# HVDCS_S3A6_48_TQFP_v1p01.net
KiCad netlist of a schematic drawn in EAGLE
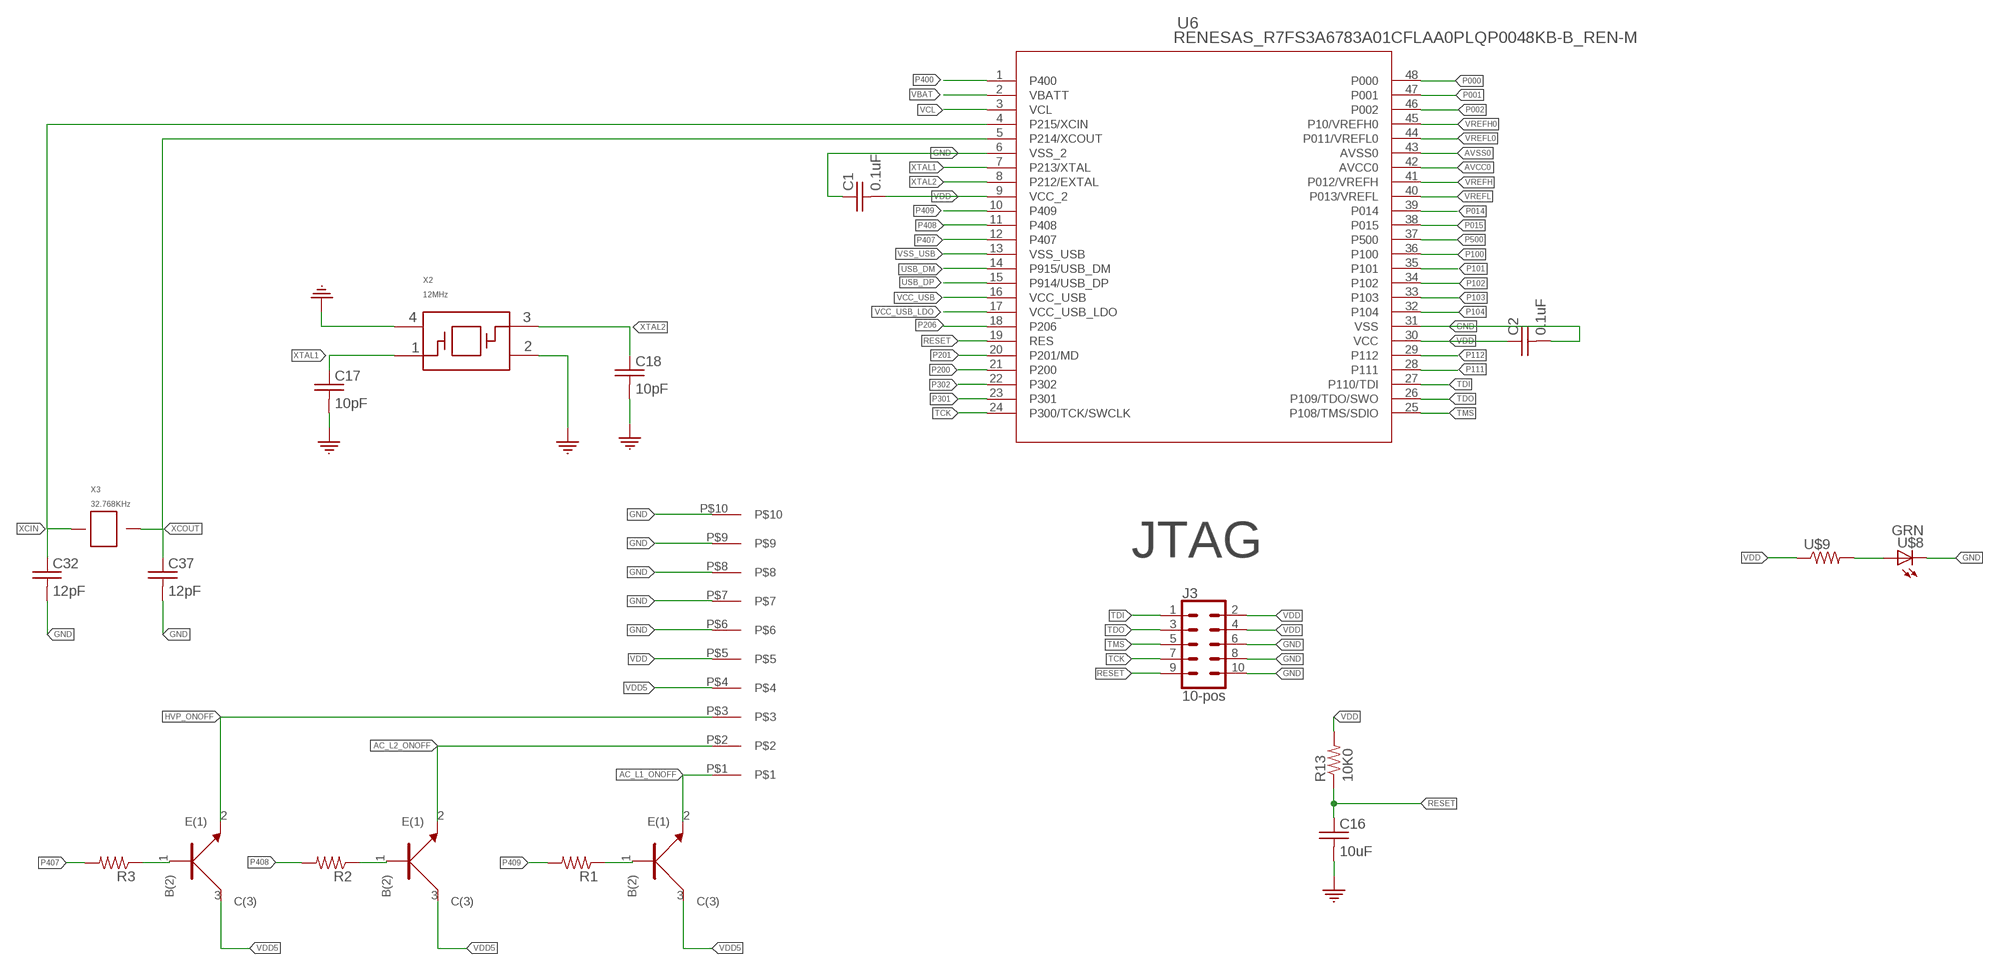
[diagram p0: schematic, sheet 1]

(export (version "E")
  (design (tool "Eeschema 10.0.6"))
  (components
    (comp (ref "C1")
      (value "0.1uF")
      (footprint "eagle-import:0402")
      (fields (field (name "PARTNO") "CL05F104ZO5NNNC"))
      (libsource (lib "eagle-import") (part "C_0402_0.1UF"))
    )
    (comp (ref "C2")
      (value "0.1uF")
      (footprint "eagle-import:0402")
      (fields (field (name "PARTNO") "CL05F104ZO5NNNC"))
      (libsource (lib "eagle-import") (part "C_0402_0.1UF"))
    )
    (comp (ref "C16")
      (value "10uF")
      (footprint "eagle-import:0402")
      (fields (field (name "PARTNO") "CL05A106MP8NUB8"))
      (libsource (lib "eagle-import") (part "C_0402_10UF"))
    )
    (comp (ref "C17")
      (value "10pF")
      (footprint "eagle-import:0402")
      (fields (field (name "PARTNO") "UMK105CG180JV-F"))
      (libsource (lib "eagle-import") (part "C_0402_18PF"))
    )
    (comp (ref "C18")
      (value "10pF")
      (footprint "eagle-import:0402")
      (fields (field (name "PARTNO") "UMK105CG180JV-F"))
      (libsource (lib "eagle-import") (part "C_0402_18PF"))
    )
    (comp (ref "C32")
      (value "12pF")
      (footprint "eagle-import:0402")
      (fields (field (name "PARTNO") "CL05C120JB5NNNC"))
      (libsource (lib "eagle-import") (part "C_0402_12PF"))
    )
    (comp (ref "C37")
      (value "12pF")
      (footprint "eagle-import:0402")
      (fields (field (name "PARTNO") "CL05C120JB5NNNC"))
      (libsource (lib "eagle-import") (part "C_0402_12PF"))
    )
    (comp (ref "J3")
      (value "10-pos")
      (footprint "eagle-import:2X5")
      (fields (field (name "PARTNO") "PH2RA-10-UA"))
      (libsource (lib "eagle-import") (part "CONN_05X2_RAPTH"))
    )
    (comp (ref "R1")
      (value "R_0402")
      (footprint "eagle-import:0402")
      (libsource (lib "eagle-import") (part "R_0402"))
    )
    (comp (ref "R2")
      (value "R_0402")
      (footprint "eagle-import:0402")
      (libsource (lib "eagle-import") (part "R_0402"))
    )
    (comp (ref "R3")
      (value "R_0402")
      (footprint "eagle-import:0402")
      (libsource (lib "eagle-import") (part "R_0402"))
    )
    (comp (ref "R13")
      (value "10K0")
      (footprint "eagle-import:0402")
      (fields (field (name "PARTNO") "RMCF0402JT10K0"))
      (libsource (lib "eagle-import") (part "R_0402_10K0"))
    )
    (comp (ref "U$5")
      (value "1_X_10_HEADER_GENERIC_.1INCH")
      (footprint "eagle-import:HEADER_1_X_10_.1_INCH")
      (libsource (lib "eagle-import") (part "1_X_10_HEADER_GENERIC_.1INCH"))
    )
    (comp (ref "U$8")
      (value "LED_0805_GREEN")
      (footprint "eagle-import:LED_0805_GREEN")
      (libsource (lib "eagle-import") (part "LED_0805_GREEN"))
    )
    (comp (ref "U$9")
      (value "470R0")
      (footprint "eagle-import:0402")
      (fields (field (name "PARTNO") "RMCF0402JT470R"))
      (libsource (lib "eagle-import") (part "R_0402_470R0"))
    )
    (comp (ref "U1")
      (value "NPN")
      (footprint "eagle-import:SOT323")
      (fields (field (name "PARTNO") "BC846BW_NPN"))
      (libsource (lib "eagle-import") (part "BC846BW"))
    )
    (comp (ref "U2")
      (value "NPN")
      (footprint "eagle-import:SOT323")
      (fields (field (name "PARTNO") "BC846BW_NPN"))
      (libsource (lib "eagle-import") (part "BC846BW"))
    )
    (comp (ref "U3")
      (value "NPN")
      (footprint "eagle-import:SOT323")
      (fields (field (name "PARTNO") "BC846BW_NPN"))
      (libsource (lib "eagle-import") (part "BC846BW"))
    )
    (comp (ref "U6")
      (value "RENESAS_R7FS3A6783A01CFLAA0PLQP0048KB-B_REN-M")
      (footprint "eagle-import:PLQP0048KB-B_REN-M")
      (fields
        (field (name "MANUFACTURER_PART_NUMBER") "R7FS3A6783A01CFL#AA0")
        (field (name "COPYRIGHT") "Copyright (C) 2021 Accelerated Designs. All rights reserved")
      )
      (libsource (lib "eagle-import") (part "RENESAS_R7FS3A6783A01CFLAA0PLQP0048KB-B_REN-M"))
    )
    (comp (ref "X2")
      (value "12MHz")
      (footprint "eagle-import:SMD_3225")
      (fields (field (name "PARTNO") "FA-238 24.0000MB-C3 "))
      (libsource (lib "eagle-import") (part "XTAL_24_MHZ"))
    )
    (comp (ref "X3")
      (value "32.768KHz")
      (footprint "eagle-import:SMD_X_2_PADS")
      (fields (field (name "PARTNO") "ABS07-32.768KHZ-T"))
      (libsource (lib "eagle-import") (part "XTAL_32.768KHZ"))
    )
  )
  (nets
    (net (code "1") (name "AC_L1_ONOFF") (class "Default")
      (node (ref "U$5") (pin "P$1") (pinfunction "P$1_P$1") (pintype "bidirectional"))
      (node (ref "U1") (pin "2") (pinfunction "E(1)_2") (pintype "output"))
    )
    (net (code "2") (name "AC_L2_ONOFF") (class "Default")
      (node (ref "U$5") (pin "P$2") (pinfunction "P$2_P$2") (pintype "bidirectional"))
      (node (ref "U2") (pin "2") (pinfunction "E(1)_2") (pintype "output"))
    )
    (net (code "3") (name "AVCC0") (class "Default")
      (node (ref "U6") (pin "42") (pinfunction "AVCC0_42") (pintype "power_in"))
    )
    (net (code "4") (name "AVSS0") (class "Default")
      (node (ref "U6") (pin "43") (pinfunction "AVSS0_43") (pintype "passive"))
    )
    (net (code "5") (name "GND") (class "Default")
      (node (ref "C1") (pin "P$1") (pinfunction "1_P$1") (pintype "passive"))
      (node (ref "C16") (pin "P$2") (pinfunction "2_P$2") (pintype "passive"))
      (node (ref "C17") (pin "P$2") (pinfunction "2_P$2") (pintype "passive"))
      (node (ref "C18") (pin "P$2") (pinfunction "2_P$2") (pintype "passive"))
      (node (ref "C2") (pin "P$2") (pinfunction "2_P$2") (pintype "passive"))
      (node (ref "C32") (pin "P$2") (pinfunction "2_P$2") (pintype "passive"))
      (node (ref "C37") (pin "P$2") (pinfunction "2_P$2") (pintype "passive"))
      (node (ref "J3") (pin "10") (pinfunction "10_10") (pintype "passive"))
      (node (ref "J3") (pin "6") (pinfunction "6_6") (pintype "passive"))
      (node (ref "J3") (pin "8") (pinfunction "8_8") (pintype "passive"))
      (node (ref "U$5") (pin "P$10") (pinfunction "P$10_P$10") (pintype "bidirectional"))
      (node (ref "U$5") (pin "P$6") (pinfunction "P$6_P$6") (pintype "bidirectional"))
      (node (ref "U$5") (pin "P$7") (pinfunction "P$7_P$7") (pintype "bidirectional"))
      (node (ref "U$5") (pin "P$8") (pinfunction "P$8_P$8") (pintype "bidirectional"))
      (node (ref "U$5") (pin "P$9") (pinfunction "P$9_P$9") (pintype "bidirectional"))
      (node (ref "U$8") (pin "C") (pinfunction "C_C") (pintype "passive"))
      (node (ref "U6") (pin "31") (pinfunction "VSS_31") (pintype "passive"))
      (node (ref "U6") (pin "6") (pinfunction "VSS_2_6") (pintype "passive"))
      (node (ref "X2") (pin "2") (pinfunction "2_2") (pintype "bidirectional"))
      (node (ref "X2") (pin "4") (pinfunction "4_4") (pintype "bidirectional"))
    )
    (net (code "6") (name "HVP_ONOFF") (class "Default")
      (node (ref "U$5") (pin "P$3") (pinfunction "P$3_P$3") (pintype "bidirectional"))
      (node (ref "U3") (pin "2") (pinfunction "E(1)_2") (pintype "output"))
    )
    (net (code "7") (name "Net-(R1-1)") (class "Default")
      (node (ref "R1") (pin "P$1") (pinfunction "1_P$1") (pintype "passive"))
      (node (ref "U1") (pin "1") (pinfunction "B(2)_1") (pintype "input"))
    )
    (net (code "8") (name "Net-(R2-1)") (class "Default")
      (node (ref "R2") (pin "P$1") (pinfunction "1_P$1") (pintype "passive"))
      (node (ref "U2") (pin "1") (pinfunction "B(2)_1") (pintype "input"))
    )
    (net (code "9") (name "Net-(R3-1)") (class "Default")
      (node (ref "R3") (pin "P$1") (pinfunction "1_P$1") (pintype "passive"))
      (node (ref "U3") (pin "1") (pinfunction "B(2)_1") (pintype "input"))
    )
    (net (code "10") (name "Net-(U$9-2)") (class "Default")
      (node (ref "U$8") (pin "A") (pinfunction "A_A") (pintype "passive"))
      (node (ref "U$9") (pin "P$2") (pinfunction "2_P$2") (pintype "passive"))
    )
    (net (code "11") (name "P000") (class "Default")
      (node (ref "U6") (pin "48") (pinfunction "P000_48") (pintype "bidirectional"))
    )
    (net (code "12") (name "P001") (class "Default")
      (node (ref "U6") (pin "47") (pinfunction "P001_47") (pintype "bidirectional"))
    )
    (net (code "13") (name "P002") (class "Default")
      (node (ref "U6") (pin "46") (pinfunction "P002_46") (pintype "bidirectional"))
    )
    (net (code "14") (name "P014") (class "Default")
      (node (ref "U6") (pin "39") (pinfunction "P014_39") (pintype "bidirectional"))
    )
    (net (code "15") (name "P015") (class "Default")
      (node (ref "U6") (pin "38") (pinfunction "P015_38") (pintype "bidirectional"))
    )
    (net (code "16") (name "P100") (class "Default")
      (node (ref "U6") (pin "36") (pinfunction "P100_36") (pintype "bidirectional"))
    )
    (net (code "17") (name "P101") (class "Default")
      (node (ref "U6") (pin "35") (pinfunction "P101_35") (pintype "bidirectional"))
    )
    (net (code "18") (name "P102") (class "Default")
      (node (ref "U6") (pin "34") (pinfunction "P102_34") (pintype "bidirectional"))
    )
    (net (code "19") (name "P103") (class "Default")
      (node (ref "U6") (pin "33") (pinfunction "P103_33") (pintype "bidirectional"))
    )
    (net (code "20") (name "P104") (class "Default")
      (node (ref "U6") (pin "32") (pinfunction "P104_32") (pintype "bidirectional"))
    )
    (net (code "21") (name "P111") (class "Default")
      (node (ref "U6") (pin "28") (pinfunction "P111_28") (pintype "bidirectional"))
    )
    (net (code "22") (name "P112") (class "Default")
      (node (ref "U6") (pin "29") (pinfunction "P112_29") (pintype "bidirectional"))
    )
    (net (code "23") (name "P200") (class "Default")
      (node (ref "U6") (pin "21") (pinfunction "P200_21") (pintype "bidirectional"))
    )
    (net (code "24") (name "P201") (class "Default")
      (node (ref "U6") (pin "20") (pinfunction "P201/MD_20") (pintype "bidirectional"))
    )
    (net (code "25") (name "P206") (class "Default")
      (node (ref "U6") (pin "18") (pinfunction "P206_18") (pintype "bidirectional"))
    )
    (net (code "26") (name "P301") (class "Default")
      (node (ref "U6") (pin "23") (pinfunction "P301_23") (pintype "bidirectional"))
    )
    (net (code "27") (name "P302") (class "Default")
      (node (ref "U6") (pin "22") (pinfunction "P302_22") (pintype "bidirectional"))
    )
    (net (code "28") (name "P400") (class "Default")
      (node (ref "U6") (pin "1") (pinfunction "P400_1") (pintype "bidirectional"))
    )
    (net (code "29") (name "P407") (class "Default")
      (node (ref "R3") (pin "P$2") (pinfunction "2_P$2") (pintype "passive"))
      (node (ref "U6") (pin "12") (pinfunction "P407_12") (pintype "bidirectional"))
    )
    (net (code "30") (name "P408") (class "Default")
      (node (ref "R2") (pin "P$2") (pinfunction "2_P$2") (pintype "passive"))
      (node (ref "U6") (pin "11") (pinfunction "P408_11") (pintype "bidirectional"))
    )
    (net (code "31") (name "P409") (class "Default")
      (node (ref "R1") (pin "P$2") (pinfunction "2_P$2") (pintype "passive"))
      (node (ref "U6") (pin "10") (pinfunction "P409_10") (pintype "bidirectional"))
    )
    (net (code "32") (name "P500") (class "Default")
      (node (ref "U6") (pin "37") (pinfunction "P500_37") (pintype "bidirectional"))
    )
    (net (code "33") (name "RESET") (class "Default")
      (node (ref "C16") (pin "P$1") (pinfunction "1_P$1") (pintype "passive"))
      (node (ref "J3") (pin "9") (pinfunction "9_9") (pintype "passive"))
      (node (ref "R13") (pin "P$1") (pinfunction "1_P$1") (pintype "passive"))
      (node (ref "U6") (pin "19") (pinfunction "RES_19") (pintype "passive"))
    )
    (net (code "34") (name "TCK") (class "Default")
      (node (ref "J3") (pin "7") (pinfunction "7_7") (pintype "passive"))
      (node (ref "U6") (pin "24") (pinfunction "P300/TCK/SWCLK_24") (pintype "bidirectional"))
    )
    (net (code "35") (name "TDI") (class "Default")
      (node (ref "J3") (pin "1") (pinfunction "1_1") (pintype "passive"))
      (node (ref "U6") (pin "27") (pinfunction "P110/TDI_27") (pintype "bidirectional"))
    )
    (net (code "36") (name "TDO") (class "Default")
      (node (ref "J3") (pin "3") (pinfunction "3_3") (pintype "passive"))
      (node (ref "U6") (pin "26") (pinfunction "P109/TDO/SWO_26") (pintype "bidirectional"))
    )
    (net (code "37") (name "TMS") (class "Default")
      (node (ref "J3") (pin "5") (pinfunction "5_5") (pintype "passive"))
      (node (ref "U6") (pin "25") (pinfunction "P108/TMS/SDIO_25") (pintype "bidirectional"))
    )
    (net (code "38") (name "USB_DM") (class "Default")
      (node (ref "U6") (pin "14") (pinfunction "P915/USB_DM_14") (pintype "bidirectional"))
    )
    (net (code "39") (name "USB_DP") (class "Default")
      (node (ref "U6") (pin "15") (pinfunction "P914/USB_DP_15") (pintype "bidirectional"))
    )
    (net (code "40") (name "VBAT") (class "Default")
      (node (ref "U6") (pin "2") (pinfunction "VBATT_2") (pintype "passive"))
    )
    (net (code "41") (name "VCC_USB") (class "Default")
      (node (ref "U6") (pin "16") (pinfunction "VCC_USB_16") (pintype "power_in"))
    )
    (net (code "42") (name "VCC_USB_LDO") (class "Default")
      (node (ref "U6") (pin "17") (pinfunction "VCC_USB_LDO_17") (pintype "power_in"))
    )
    (net (code "43") (name "VCL") (class "Default")
      (node (ref "U6") (pin "3") (pinfunction "VCL_3") (pintype "passive"))
    )
    (net (code "44") (name "VDD") (class "Default")
      (node (ref "C1") (pin "P$2") (pinfunction "2_P$2") (pintype "passive"))
      (node (ref "C2") (pin "P$1") (pinfunction "1_P$1") (pintype "passive"))
      (node (ref "J3") (pin "2") (pinfunction "2_2") (pintype "passive"))
      (node (ref "J3") (pin "4") (pinfunction "4_4") (pintype "passive"))
      (node (ref "R13") (pin "P$2") (pinfunction "2_P$2") (pintype "passive"))
      (node (ref "U$5") (pin "P$5") (pinfunction "P$5_P$5") (pintype "bidirectional"))
      (node (ref "U$9") (pin "P$1") (pinfunction "1_P$1") (pintype "passive"))
      (node (ref "U6") (pin "30") (pinfunction "VCC_30") (pintype "power_in"))
      (node (ref "U6") (pin "9") (pinfunction "VCC_2_9") (pintype "power_in"))
    )
    (net (code "45") (name "VDD5") (class "Default")
      (node (ref "U$5") (pin "P$4") (pinfunction "P$4_P$4") (pintype "bidirectional"))
      (node (ref "U1") (pin "3") (pinfunction "C(3)_3") (pintype "input"))
      (node (ref "U2") (pin "3") (pinfunction "C(3)_3") (pintype "input"))
      (node (ref "U3") (pin "3") (pinfunction "C(3)_3") (pintype "input"))
    )
    (net (code "46") (name "VREFH") (class "Default")
      (node (ref "U6") (pin "41") (pinfunction "P012/VREFH_41") (pintype "power_in"))
    )
    (net (code "47") (name "VREFH0") (class "Default")
      (node (ref "U6") (pin "45") (pinfunction "P10/VREFH0_45") (pintype "power_in"))
    )
    (net (code "48") (name "VREFL") (class "Default")
      (node (ref "U6") (pin "40") (pinfunction "P013/VREFL_40") (pintype "power_in"))
    )
    (net (code "49") (name "VREFL0") (class "Default")
      (node (ref "U6") (pin "44") (pinfunction "P011/VREFL0_44") (pintype "power_in"))
    )
    (net (code "50") (name "VSS_USB") (class "Default")
      (node (ref "U6") (pin "13") (pinfunction "VSS_USB_13") (pintype "passive"))
    )
    (net (code "51") (name "XCIN") (class "Default")
      (node (ref "C32") (pin "P$1") (pinfunction "1_P$1") (pintype "passive"))
      (node (ref "U6") (pin "4") (pinfunction "P215/XCIN_4") (pintype "bidirectional"))
      (node (ref "X3") (pin "P$1") (pinfunction "P$1_P$1") (pintype "bidirectional"))
    )
    (net (code "52") (name "XCOUT") (class "Default")
      (node (ref "C37") (pin "P$1") (pinfunction "1_P$1") (pintype "passive"))
      (node (ref "U6") (pin "5") (pinfunction "P214/XCOUT_5") (pintype "output"))
      (node (ref "X3") (pin "P$2") (pinfunction "P$2_P$2") (pintype "bidirectional"))
    )
    (net (code "53") (name "XTAL1") (class "Default")
      (node (ref "C17") (pin "P$1") (pinfunction "1_P$1") (pintype "passive"))
      (node (ref "U6") (pin "7") (pinfunction "P213/XTAL_7") (pintype "bidirectional"))
      (node (ref "X2") (pin "1") (pinfunction "1_1") (pintype "bidirectional"))
    )
    (net (code "54") (name "XTAL2") (class "Default")
      (node (ref "C18") (pin "P$1") (pinfunction "1_P$1") (pintype "passive"))
      (node (ref "U6") (pin "8") (pinfunction "P212/EXTAL_8") (pintype "bidirectional"))
      (node (ref "X2") (pin "3") (pinfunction "3_3") (pintype "bidirectional"))
    )
  )
)
